# TG3_1.net
KiCad netlist of a schematic drawn in EAGLE
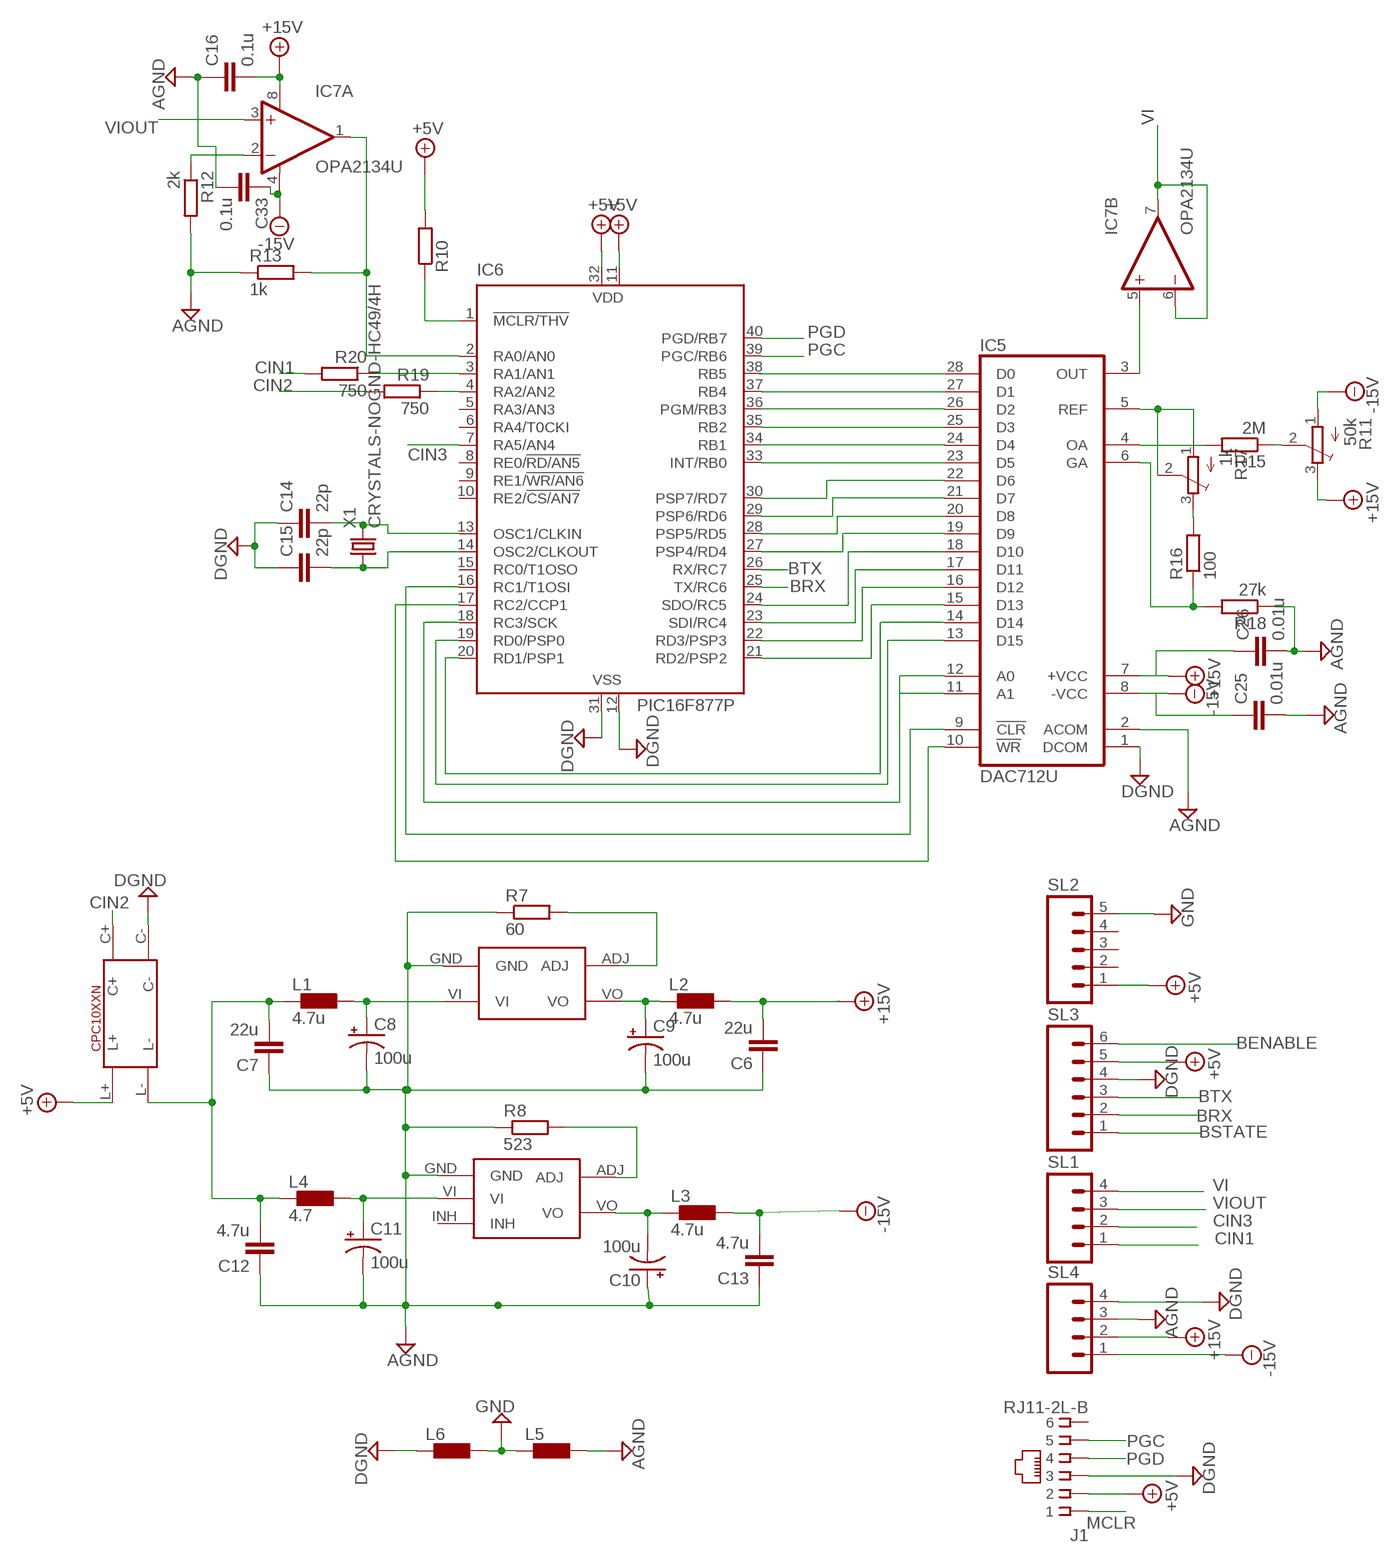
[diagram p0: schematic, sheet 1]

(export (version "E")
  (design (tool "Eeschema 10.0.6"))
  (components
    (comp (ref "C6")
      (value "22u")
      (footprint "eagle-import:C0805")
      (libsource (lib "eagle-import") (part "C"))
    )
    (comp (ref "C7")
      (value "22u")
      (footprint "eagle-import:C0805")
      (libsource (lib "eagle-import") (part "C"))
    )
    (comp (ref "C8")
      (value "100u")
      (footprint "eagle-import:150CLZ-0810")
      (libsource (lib "eagle-import") (part "CPOL-US150CLZ-0810"))
    )
    (comp (ref "C9")
      (value "100u")
      (footprint "eagle-import:150CLZ-0810")
      (libsource (lib "eagle-import") (part "CPOL-US150CLZ-0810"))
    )
    (comp (ref "C10")
      (value "100u")
      (footprint "eagle-import:150CLZ-0810")
      (libsource (lib "eagle-import") (part "CPOL-US150CLZ-0810"))
    )
    (comp (ref "C11")
      (value "100u")
      (footprint "eagle-import:150CLZ-0810")
      (libsource (lib "eagle-import") (part "CPOL-US150CLZ-0810"))
    )
    (comp (ref "C12")
      (value "4.7u")
      (footprint "eagle-import:C0805")
      (libsource (lib "eagle-import") (part "C"))
    )
    (comp (ref "C13")
      (value "4.7u")
      (footprint "eagle-import:C0805")
      (libsource (lib "eagle-import") (part "C"))
    )
    (comp (ref "C14")
      (value "22p")
      (footprint "eagle-import:C0805")
      (libsource (lib "eagle-import") (part "C"))
    )
    (comp (ref "C15")
      (value "22p")
      (footprint "eagle-import:C0805")
      (libsource (lib "eagle-import") (part "C"))
    )
    (comp (ref "C16")
      (value "0.1u")
      (footprint "eagle-import:C0805")
      (libsource (lib "eagle-import") (part "C"))
    )
    (comp (ref "C25")
      (value "0.01u")
      (footprint "eagle-import:C0805")
      (libsource (lib "eagle-import") (part "C"))
    )
    (comp (ref "C26")
      (value "0.01u")
      (footprint "eagle-import:C0805")
      (libsource (lib "eagle-import") (part "C"))
    )
    (comp (ref "C33")
      (value "0.1u")
      (footprint "eagle-import:C0805")
      (libsource (lib "eagle-import") (part "C"))
    )
    (comp (ref "IC5")
      (value "DAC712U")
      (footprint "eagle-import:SO28-3")
      (fields (field (name "MF") "TEXAS INSTRUMENTS"))
      (libsource (lib "eagle-import") (part "DAC712U"))
    )
    (comp (ref "IC6")
      (value "PIC16F877P")
      (footprint "eagle-import:DIL40")
      (fields (field (name "MF") "MICROCHIP") (field (name "MPN") "PIC16F877-04/P"))
      (libsource (lib "eagle-import") (part "PIC16F87P7"))
    )
    (comp (ref "IC7")
      (value "OPA2134U")
      (footprint "eagle-import:SO08")
      (fields (field (name "MF") "TEXAS INSTRUMENTS") (field (name "MPN") "OPA2134UA"))
      (libsource (lib "eagle-import") (part "OPA2134U"))
    )
    (comp (ref "J1")
      (value "RJ11-2L-B")
      (footprint "eagle-import:RJ11-NO_SHIELD")
      (fields (field (name "MF") "TYCO ELECTRONICS"))
      (libsource (lib "eagle-import") (part "RJ11-2L-B"))
    )
    (comp (ref "L1")
      (value "4.7u")
      (footprint "eagle-import:L2012C")
      (libsource (lib "eagle-import") (part "LL2012C"))
    )
    (comp (ref "L2")
      (value "4.7u")
      (footprint "eagle-import:L2012C")
      (libsource (lib "eagle-import") (part "LL2012C"))
    )
    (comp (ref "L3")
      (value "4.7u")
      (footprint "eagle-import:L2012C")
      (libsource (lib "eagle-import") (part "LL2012C"))
    )
    (comp (ref "L4")
      (value "4.7")
      (footprint "eagle-import:L2012C")
      (libsource (lib "eagle-import") (part "LL2012C"))
    )
    (comp (ref "L5")
      (value "LL2012C")
      (footprint "eagle-import:L2012C")
      (libsource (lib "eagle-import") (part "LL2012C"))
    )
    (comp (ref "L6")
      (value "LL2012C")
      (footprint "eagle-import:L2012C")
      (libsource (lib "eagle-import") (part "LL2012C"))
    )
    (comp (ref "R7")
      (value "60")
      (footprint "eagle-import:R0805")
      (libsource (lib "eagle-import") (part "R"))
    )
    (comp (ref "R8")
      (value "523")
      (footprint "eagle-import:R0805")
      (libsource (lib "eagle-import") (part "R"))
    )
    (comp (ref "R10")
      (value "R")
      (footprint "eagle-import:R0805")
      (libsource (lib "eagle-import") (part "R"))
    )
    (comp (ref "R11")
      (value "50k")
      (footprint "eagle-import:3223W")
      (libsource (lib "eagle-import") (part "TRIM_EU-3223W"))
    )
    (comp (ref "R12")
      (value "2k")
      (footprint "eagle-import:R0805")
      (libsource (lib "eagle-import") (part "R"))
    )
    (comp (ref "R13")
      (value "1k")
      (footprint "eagle-import:R0805")
      (libsource (lib "eagle-import") (part "R"))
    )
    (comp (ref "R15")
      (value "2M")
      (footprint "eagle-import:R0805")
      (libsource (lib "eagle-import") (part "R"))
    )
    (comp (ref "R16")
      (value "100")
      (footprint "eagle-import:R0805")
      (libsource (lib "eagle-import") (part "R"))
    )
    (comp (ref "R17")
      (value "1k")
      (footprint "eagle-import:3223W")
      (libsource (lib "eagle-import") (part "TRIM_EU-3223W"))
    )
    (comp (ref "R18")
      (value "27k")
      (footprint "eagle-import:R0805")
      (libsource (lib "eagle-import") (part "R"))
    )
    (comp (ref "R19")
      (value "750")
      (footprint "eagle-import:R0805")
      (libsource (lib "eagle-import") (part "R"))
    )
    (comp (ref "R20")
      (value "750")
      (footprint "eagle-import:R0805")
      (libsource (lib "eagle-import") (part "R"))
    )
    (comp (ref "SL1")
      (value "M04")
      (footprint "eagle-import:04P")
      (libsource (lib "eagle-import") (part "M04"))
    )
    (comp (ref "SL2")
      (value "M05")
      (footprint "eagle-import:05P")
      (libsource (lib "eagle-import") (part "M05"))
    )
    (comp (ref "SL3")
      (value "M06")
      (footprint "eagle-import:06P")
      (libsource (lib "eagle-import") (part "M06"))
    )
    (comp (ref "SL4")
      (value "M04")
      (footprint "eagle-import:04P")
      (libsource (lib "eagle-import") (part "M04"))
    )
    (comp (ref "U$1")
      (value "PTN04050C")
      (footprint "eagle-import:PTN04050C")
      (libsource (lib "eagle-import") (part "PTN04050C"))
    )
    (comp (ref "U$2")
      (value "PTN04050A")
      (footprint "eagle-import:PTN04050A")
      (libsource (lib "eagle-import") (part "PTN04050A"))
    )
    (comp (ref "U$6")
      (value "CPC10XXN")
      (footprint "eagle-import:CPC10XXN")
      (libsource (lib "eagle-import") (part "CPC10XXN"))
    )
    (comp (ref "X1")
      (value "CRYSTALS-NOGND-HC49/4H")
      (footprint "eagle-import:HC49")
      (libsource (lib "eagle-import") (part "CRYSTALS-NOGND-HC49/4H"))
    )
  )
  (nets
    (net (code "1") (name "+5V") (class "Default")
      (node (ref "IC6") (pin "11") (pinfunction "VDD_11") (pintype "power_in"))
      (node (ref "IC6") (pin "32") (pinfunction "VDD_32") (pintype "power_in"))
      (node (ref "J1") (pin "2") (pinfunction "2_2") (pintype "passive"))
      (node (ref "R10") (pin "2") (pinfunction "2_2") (pintype "passive"))
      (node (ref "SL2") (pin "1") (pinfunction "1_1") (pintype "passive"))
      (node (ref "SL3") (pin "5") (pinfunction "5_5") (pintype "passive"))
      (node (ref "U$6") (pin "L+") (pinfunction "L+_L+") (pintype "bidirectional"))
    )
    (net (code "2") (name "+15V") (class "Default")
      (node (ref "C16") (pin "2") (pinfunction "2_2") (pintype "passive"))
      (node (ref "C26") (pin "1") (pinfunction "1_1") (pintype "passive"))
      (node (ref "C6") (pin "2") (pinfunction "2_2") (pintype "passive"))
      (node (ref "IC5") (pin "7") (pinfunction "+VCC_7") (pintype "power_in"))
      (node (ref "IC7") (pin "8") (pinfunction "V+_8") (pintype "power_in"))
      (node (ref "L2") (pin "1") (pinfunction "1_1") (pintype "passive"))
      (node (ref "R11") (pin "3") (pinfunction "E_3") (pintype "passive"))
      (node (ref "SL4") (pin "2") (pinfunction "2_2") (pintype "passive"))
    )
    (net (code "3") (name "-15V") (class "Default")
      (node (ref "C13") (pin "2") (pinfunction "2_2") (pintype "passive"))
      (node (ref "C25") (pin "1") (pinfunction "1_1") (pintype "passive"))
      (node (ref "C33") (pin "1") (pinfunction "1_1") (pintype "passive"))
      (node (ref "IC5") (pin "8") (pinfunction "-VCC_8") (pintype "power_in"))
      (node (ref "IC7") (pin "4") (pinfunction "V-_4") (pintype "power_in"))
      (node (ref "L3") (pin "1") (pinfunction "1_1") (pintype "passive"))
      (node (ref "R11") (pin "1") (pinfunction "A_1") (pintype "passive"))
      (node (ref "SL4") (pin "1") (pinfunction "1_1") (pintype "passive"))
    )
    (net (code "4") (name "/BENABLE") (class "Default")
      (node (ref "SL3") (pin "6") (pinfunction "6_6") (pintype "passive"))
    )
    (net (code "5") (name "/BRX") (class "Default")
      (node (ref "IC6") (pin "25") (pinfunction "TX/RC6_25") (pintype "bidirectional"))
      (node (ref "SL3") (pin "2") (pinfunction "2_2") (pintype "passive"))
    )
    (net (code "6") (name "/BSTATE") (class "Default")
      (node (ref "SL3") (pin "1") (pinfunction "1_1") (pintype "passive"))
    )
    (net (code "7") (name "/BTX") (class "Default")
      (node (ref "IC6") (pin "26") (pinfunction "RX/RC7_26") (pintype "bidirectional"))
      (node (ref "SL3") (pin "3") (pinfunction "3_3") (pintype "passive"))
    )
    (net (code "8") (name "/CIN1") (class "Default")
      (node (ref "R20") (pin "2") (pinfunction "2_2") (pintype "passive"))
      (node (ref "SL1") (pin "1") (pinfunction "1_1") (pintype "passive"))
    )
    (net (code "9") (name "/CIN2") (class "Default")
      (node (ref "R19") (pin "2") (pinfunction "2_2") (pintype "passive"))
      (node (ref "U$6") (pin "C+") (pinfunction "C+_C+") (pintype "bidirectional"))
    )
    (net (code "10") (name "/CIN3") (class "Default")
      (node (ref "IC6") (pin "7") (pinfunction "RA5/AN4_7") (pintype "bidirectional"))
      (node (ref "SL1") (pin "2") (pinfunction "2_2") (pintype "passive"))
    )
    (net (code "11") (name "/MCLR") (class "Default")
      (node (ref "IC6") (pin "1") (pinfunction "~{MCLR/THV}_1") (pintype "input"))
      (node (ref "J1") (pin "1") (pinfunction "1_1") (pintype "passive"))
      (node (ref "R10") (pin "1") (pinfunction "1_1") (pintype "passive"))
    )
    (net (code "12") (name "/PGC") (class "Default")
      (node (ref "IC6") (pin "39") (pinfunction "PGC/RB6_39") (pintype "bidirectional"))
      (node (ref "J1") (pin "5") (pinfunction "5_5") (pintype "passive"))
    )
    (net (code "13") (name "/PGD") (class "Default")
      (node (ref "IC6") (pin "40") (pinfunction "PGD/RB7_40") (pintype "bidirectional"))
      (node (ref "J1") (pin "4") (pinfunction "4_4") (pintype "passive"))
    )
    (net (code "14") (name "/VI") (class "Default")
      (node (ref "IC7") (pin "6") (pinfunction "-IN_6") (pintype "input"))
      (node (ref "IC7") (pin "7") (pinfunction "OUT_7") (pintype "output"))
      (node (ref "SL1") (pin "4") (pinfunction "4_4") (pintype "passive"))
    )
    (net (code "15") (name "/VIOUT") (class "Default")
      (node (ref "IC7") (pin "3") (pinfunction "+IN_3") (pintype "input"))
      (node (ref "SL1") (pin "3") (pinfunction "3_3") (pintype "passive"))
    )
    (net (code "16") (name "AGND") (class "Default")
      (node (ref "C10") (pin "+") (pinfunction "+_+") (pintype "passive"))
      (node (ref "C11") (pin "-") (pinfunction "-_-") (pintype "passive"))
      (node (ref "C12") (pin "1") (pinfunction "1_1") (pintype "passive"))
      (node (ref "C13") (pin "1") (pinfunction "1_1") (pintype "passive"))
      (node (ref "C16") (pin "1") (pinfunction "1_1") (pintype "passive"))
      (node (ref "C25") (pin "2") (pinfunction "2_2") (pintype "passive"))
      (node (ref "C26") (pin "2") (pinfunction "2_2") (pintype "passive"))
      (node (ref "C33") (pin "2") (pinfunction "2_2") (pintype "passive"))
      (node (ref "C6") (pin "1") (pinfunction "1_1") (pintype "passive"))
      (node (ref "C7") (pin "1") (pinfunction "1_1") (pintype "passive"))
      (node (ref "C8") (pin "-") (pinfunction "-_-") (pintype "passive"))
      (node (ref "C9") (pin "-") (pinfunction "-_-") (pintype "passive"))
      (node (ref "IC5") (pin "2") (pinfunction "ACOM_2") (pintype "power_in"))
      (node (ref "L5") (pin "1") (pinfunction "1_1") (pintype "passive"))
      (node (ref "R12") (pin "2") (pinfunction "2_2") (pintype "passive"))
      (node (ref "R13") (pin "1") (pinfunction "1_1") (pintype "passive"))
      (node (ref "R18") (pin "1") (pinfunction "1_1") (pintype "passive"))
      (node (ref "R7") (pin "1") (pinfunction "1_1") (pintype "passive"))
      (node (ref "R8") (pin "1") (pinfunction "1_1") (pintype "passive"))
      (node (ref "SL4") (pin "3") (pinfunction "3_3") (pintype "passive"))
      (node (ref "U$1") (pin "GND") (pinfunction "GND_GND") (pintype "bidirectional"))
      (node (ref "U$2") (pin "GND") (pinfunction "GND_GND") (pintype "bidirectional"))
    )
    (net (code "17") (name "DGND") (class "Default")
      (node (ref "C14") (pin "1") (pinfunction "1_1") (pintype "passive"))
      (node (ref "C15") (pin "1") (pinfunction "1_1") (pintype "passive"))
      (node (ref "IC5") (pin "1") (pinfunction "DCOM_1") (pintype "power_in"))
      (node (ref "IC6") (pin "12") (pinfunction "VSS_12") (pintype "power_in"))
      (node (ref "IC6") (pin "31") (pinfunction "VSS_31") (pintype "power_in"))
      (node (ref "J1") (pin "3") (pinfunction "3_3") (pintype "passive"))
      (node (ref "L6") (pin "2") (pinfunction "2_2") (pintype "passive"))
      (node (ref "SL3") (pin "4") (pinfunction "4_4") (pintype "passive"))
      (node (ref "SL4") (pin "4") (pinfunction "4_4") (pintype "passive"))
      (node (ref "U$6") (pin "C-") (pinfunction "C-_C-") (pintype "bidirectional"))
    )
    (net (code "18") (name "GND") (class "Default")
      (node (ref "L5") (pin "2") (pinfunction "2_2") (pintype "passive"))
      (node (ref "L6") (pin "1") (pinfunction "1_1") (pintype "passive"))
      (node (ref "SL2") (pin "5") (pinfunction "5_5") (pintype "passive"))
    )
    (net (code "19") (name "Net-(C8-Pad+)") (class "Default")
      (node (ref "C8") (pin "+") (pinfunction "+_+") (pintype "passive"))
      (node (ref "L1") (pin "1") (pinfunction "1_1") (pintype "passive"))
      (node (ref "U$1") (pin "VI") (pinfunction "VI_VI") (pintype "bidirectional"))
    )
    (net (code "20") (name "Net-(C9-Pad+)") (class "Default")
      (node (ref "C9") (pin "+") (pinfunction "+_+") (pintype "passive"))
      (node (ref "L2") (pin "2") (pinfunction "2_2") (pintype "passive"))
      (node (ref "U$1") (pin "VO") (pinfunction "VO_VO") (pintype "bidirectional"))
    )
    (net (code "21") (name "Net-(C10-Pad-)") (class "Default")
      (node (ref "C10") (pin "-") (pinfunction "-_-") (pintype "passive"))
      (node (ref "L3") (pin "2") (pinfunction "2_2") (pintype "passive"))
      (node (ref "U$2") (pin "VO") (pinfunction "VO_VO") (pintype "bidirectional"))
    )
    (net (code "22") (name "Net-(C11-Pad+)") (class "Default")
      (node (ref "C11") (pin "+") (pinfunction "+_+") (pintype "passive"))
      (node (ref "L4") (pin "1") (pinfunction "1_1") (pintype "passive"))
      (node (ref "U$2") (pin "VI") (pinfunction "VI_VI") (pintype "bidirectional"))
    )
    (net (code "23") (name "Net-(C12-Pad2)") (class "Default")
      (node (ref "C12") (pin "2") (pinfunction "2_2") (pintype "passive"))
      (node (ref "C7") (pin "2") (pinfunction "2_2") (pintype "passive"))
      (node (ref "L1") (pin "2") (pinfunction "2_2") (pintype "passive"))
      (node (ref "L4") (pin "2") (pinfunction "2_2") (pintype "passive"))
      (node (ref "U$6") (pin "L-") (pinfunction "L-_L-") (pintype "bidirectional"))
    )
    (net (code "24") (name "Net-(IC5-A0)") (class "Default")
      (node (ref "IC5") (pin "11") (pinfunction "A1_11") (pintype "input"))
      (node (ref "IC5") (pin "12") (pinfunction "A0_12") (pintype "input"))
      (node (ref "IC6") (pin "18") (pinfunction "RC3/SCK_18") (pintype "bidirectional"))
    )
    (net (code "25") (name "Net-(IC5-D1)") (class "Default")
      (node (ref "IC5") (pin "27") (pinfunction "D1_27") (pintype "input"))
      (node (ref "IC6") (pin "37") (pinfunction "RB4_37") (pintype "bidirectional"))
    )
    (net (code "26") (name "Net-(IC5-D2)") (class "Default")
      (node (ref "IC5") (pin "26") (pinfunction "D2_26") (pintype "input"))
      (node (ref "IC6") (pin "36") (pinfunction "PGM/RB3_36") (pintype "bidirectional"))
    )
    (net (code "27") (name "Net-(IC5-D3)") (class "Default")
      (node (ref "IC5") (pin "25") (pinfunction "D3_25") (pintype "input"))
      (node (ref "IC6") (pin "35") (pinfunction "RB2_35") (pintype "bidirectional"))
    )
    (net (code "28") (name "Net-(IC5-D4)") (class "Default")
      (node (ref "IC5") (pin "24") (pinfunction "D4_24") (pintype "input"))
      (node (ref "IC6") (pin "34") (pinfunction "RB1_34") (pintype "bidirectional"))
    )
    (net (code "29") (name "Net-(IC5-D5)") (class "Default")
      (node (ref "IC5") (pin "23") (pinfunction "D5_23") (pintype "input"))
      (node (ref "IC6") (pin "33") (pinfunction "INT/RB0_33") (pintype "bidirectional"))
    )
    (net (code "30") (name "Net-(IC5-D6)") (class "Default")
      (node (ref "IC5") (pin "22") (pinfunction "D6_22") (pintype "input"))
      (node (ref "IC6") (pin "30") (pinfunction "PSP7/RD7_30") (pintype "bidirectional"))
    )
    (net (code "31") (name "Net-(IC5-D7)") (class "Default")
      (node (ref "IC5") (pin "21") (pinfunction "D7_21") (pintype "input"))
      (node (ref "IC6") (pin "29") (pinfunction "PSP6/RD6_29") (pintype "bidirectional"))
    )
    (net (code "32") (name "Net-(IC5-D8)") (class "Default")
      (node (ref "IC5") (pin "20") (pinfunction "D8_20") (pintype "input"))
      (node (ref "IC6") (pin "28") (pinfunction "PSP5/RD5_28") (pintype "bidirectional"))
    )
    (net (code "33") (name "Net-(IC5-D9)") (class "Default")
      (node (ref "IC5") (pin "19") (pinfunction "D9_19") (pintype "input"))
      (node (ref "IC6") (pin "27") (pinfunction "PSP4/RD4_27") (pintype "bidirectional"))
    )
    (net (code "34") (name "Net-(IC5-D10)") (class "Default")
      (node (ref "IC5") (pin "18") (pinfunction "D10_18") (pintype "input"))
      (node (ref "IC6") (pin "24") (pinfunction "SDO/RC5_24") (pintype "bidirectional"))
    )
    (net (code "35") (name "Net-(IC5-D11)") (class "Default")
      (node (ref "IC5") (pin "17") (pinfunction "D11_17") (pintype "input"))
      (node (ref "IC6") (pin "23") (pinfunction "SDI/RC4_23") (pintype "bidirectional"))
    )
    (net (code "36") (name "Net-(IC5-D12)") (class "Default")
      (node (ref "IC5") (pin "16") (pinfunction "D12_16") (pintype "input"))
      (node (ref "IC6") (pin "22") (pinfunction "RD3/PSP3_22") (pintype "bidirectional"))
    )
    (net (code "37") (name "Net-(IC5-D13)") (class "Default")
      (node (ref "IC5") (pin "15") (pinfunction "D13_15") (pintype "input"))
      (node (ref "IC6") (pin "21") (pinfunction "RD2/PSP2_21") (pintype "bidirectional"))
    )
    (net (code "38") (name "Net-(IC5-D14)") (class "Default")
      (node (ref "IC5") (pin "14") (pinfunction "D14_14") (pintype "input"))
      (node (ref "IC6") (pin "20") (pinfunction "RD1/PSP1_20") (pintype "bidirectional"))
    )
    (net (code "39") (name "Net-(IC5-D15)") (class "Default")
      (node (ref "IC5") (pin "13") (pinfunction "D15_13") (pintype "input"))
      (node (ref "IC6") (pin "19") (pinfunction "RD0/PSP0_19") (pintype "bidirectional"))
    )
    (net (code "40") (name "Net-(IC5-GA)") (class "Default")
      (node (ref "IC5") (pin "6") (pinfunction "GA_6") (pintype "passive"))
      (node (ref "R16") (pin "1") (pinfunction "1_1") (pintype "passive"))
      (node (ref "R18") (pin "2") (pinfunction "2_2") (pintype "passive"))
    )
    (net (code "41") (name "Net-(IC5-OA)") (class "Default")
      (node (ref "IC5") (pin "4") (pinfunction "OA_4") (pintype "passive"))
      (node (ref "R15") (pin "2") (pinfunction "2_2") (pintype "passive"))
    )
    (net (code "42") (name "Net-(IC5-OUT)") (class "Default")
      (node (ref "IC5") (pin "3") (pinfunction "OUT_3") (pintype "output"))
      (node (ref "IC7") (pin "5") (pinfunction "+IN_5") (pintype "input"))
    )
    (net (code "43") (name "Net-(IC5-REF)") (class "Default")
      (node (ref "IC5") (pin "5") (pinfunction "REF_5") (pintype "output"))
      (node (ref "R17") (pin "1") (pinfunction "A_1") (pintype "passive"))
      (node (ref "R17") (pin "2") (pinfunction "S_2") (pintype "passive"))
    )
    (net (code "44") (name "Net-(IC5-~{CLR})") (class "Default")
      (node (ref "IC5") (pin "9") (pinfunction "~{CLR}_9") (pintype "input"))
      (node (ref "IC6") (pin "16") (pinfunction "RC1/T1OSI_16") (pintype "bidirectional"))
    )
    (net (code "45") (name "Net-(IC5-~{WR})") (class "Default")
      (node (ref "IC5") (pin "10") (pinfunction "~{WR}_10") (pintype "input"))
      (node (ref "IC6") (pin "17") (pinfunction "RC2/CCP1_17") (pintype "bidirectional"))
    )
    (net (code "46") (name "Net-(IC6-OSC1{slash}CLKIN)") (class "Default")
      (node (ref "C14") (pin "2") (pinfunction "2_2") (pintype "passive"))
      (node (ref "IC6") (pin "13") (pinfunction "OSC1/CLKIN_13") (pintype "input"))
      (node (ref "X1") (pin "2") (pinfunction "2_2") (pintype "passive"))
    )
    (net (code "47") (name "Net-(IC6-OSC2{slash}CLKOUT)") (class "Default")
      (node (ref "C15") (pin "2") (pinfunction "2_2") (pintype "passive"))
      (node (ref "IC6") (pin "14") (pinfunction "OSC2/CLKOUT_14") (pintype "output"))
      (node (ref "X1") (pin "1") (pinfunction "1_1") (pintype "passive"))
    )
    (net (code "48") (name "Net-(IC6-RA0{slash}AN0)") (class "Default")
      (node (ref "IC6") (pin "2") (pinfunction "RA0/AN0_2") (pintype "bidirectional"))
      (node (ref "IC7") (pin "1") (pinfunction "OUT_1") (pintype "output"))
      (node (ref "R13") (pin "2") (pinfunction "2_2") (pintype "passive"))
    )
    (net (code "49") (name "Net-(IC6-RA1{slash}AN1)") (class "Default")
      (node (ref "IC6") (pin "3") (pinfunction "RA1/AN1_3") (pintype "bidirectional"))
      (node (ref "R20") (pin "1") (pinfunction "1_1") (pintype "passive"))
    )
    (net (code "50") (name "Net-(IC6-RA2{slash}AN2)") (class "Default")
      (node (ref "IC6") (pin "4") (pinfunction "RA2/AN2_4") (pintype "bidirectional"))
      (node (ref "R19") (pin "1") (pinfunction "1_1") (pintype "passive"))
    )
    (net (code "51") (name "Net-(IC7A--IN)") (class "Default")
      (node (ref "IC7") (pin "2") (pinfunction "-IN_2") (pintype "input"))
      (node (ref "R12") (pin "1") (pinfunction "1_1") (pintype "passive"))
    )
    (net (code "52") (name "Net-(R7-Pad2)") (class "Default")
      (node (ref "R7") (pin "2") (pinfunction "2_2") (pintype "passive"))
      (node (ref "U$1") (pin "ADJ") (pinfunction "ADJ_ADJ") (pintype "bidirectional"))
    )
    (net (code "53") (name "Net-(R8-Pad2)") (class "Default")
      (node (ref "R8") (pin "2") (pinfunction "2_2") (pintype "passive"))
      (node (ref "U$2") (pin "ADJ") (pinfunction "ADJ_ADJ") (pintype "bidirectional"))
    )
    (net (code "54") (name "Net-(R11-S)") (class "Default")
      (node (ref "R11") (pin "2") (pinfunction "S_2") (pintype "passive"))
      (node (ref "R15") (pin "1") (pinfunction "1_1") (pintype "passive"))
    )
    (net (code "55") (name "Net-(R17-E)") (class "Default")
      (node (ref "R16") (pin "2") (pinfunction "2_2") (pintype "passive"))
      (node (ref "R17") (pin "3") (pinfunction "E_3") (pintype "passive"))
    )
    (net (code "56") (name "unconnected-(IC5-D0-Pad28)") (class "Default")
      (node (ref "IC5") (pin "28") (pinfunction "D0_28") (pintype "input"))
    )
    (net (code "57") (name "unconnected-(IC6-RA3{slash}AN3-Pad5)") (class "Default")
      (node (ref "IC6") (pin "5") (pinfunction "RA3/AN3_5") (pintype "bidirectional"))
    )
    (net (code "58") (name "unconnected-(IC6-RA4{slash}T0CKI-Pad6)") (class "Default")
      (node (ref "IC6") (pin "6") (pinfunction "RA4/T0CKI_6") (pintype "bidirectional"))
    )
    (net (code "59") (name "unconnected-(IC6-RB5-Pad38)") (class "Default")
      (node (ref "IC6") (pin "38") (pinfunction "RB5_38") (pintype "bidirectional"))
    )
    (net (code "60") (name "unconnected-(IC6-RC0{slash}T1OSO-Pad15)") (class "Default")
      (node (ref "IC6") (pin "15") (pinfunction "RC0/T1OSO_15") (pintype "bidirectional"))
    )
    (net (code "61") (name "unconnected-(IC6-RE0{slash}~{RD{slash}AN5}-Pad8)") (class "Default")
      (node (ref "IC6") (pin "8") (pinfunction "RE0/~{RD/AN5}_8") (pintype "bidirectional"))
    )
    (net (code "62") (name "unconnected-(IC6-RE1{slash}~{WR{slash}AN6}-Pad9)") (class "Default")
      (node (ref "IC6") (pin "9") (pinfunction "RE1/~{WR/AN6}_9") (pintype "bidirectional"))
    )
    (net (code "63") (name "unconnected-(IC6-RE2{slash}~{CS{slash}AN7}-Pad10)") (class "Default")
      (node (ref "IC6") (pin "10") (pinfunction "RE2/~{CS/AN7}_10") (pintype "bidirectional"))
    )
    (net (code "64") (name "unconnected-(J1-Pad6)") (class "Default")
      (node (ref "J1") (pin "6") (pinfunction "6_6") (pintype "passive"))
    )
    (net (code "65") (name "unconnected-(SL2-Pad2)") (class "Default")
      (node (ref "SL2") (pin "2") (pinfunction "2_2") (pintype "passive"))
    )
    (net (code "66") (name "unconnected-(SL2-Pad3)") (class "Default")
      (node (ref "SL2") (pin "3") (pinfunction "3_3") (pintype "passive"))
    )
    (net (code "67") (name "unconnected-(SL2-Pad4)") (class "Default")
      (node (ref "SL2") (pin "4") (pinfunction "4_4") (pintype "passive"))
    )
    (net (code "68") (name "unconnected-(U$2-PadINH)") (class "Default")
      (node (ref "U$2") (pin "INH") (pinfunction "INH_INH") (pintype "bidirectional"))
    )
  )
)
